# HS_MASTER_V3.net
KiCad netlist of a schematic drawn in EAGLE
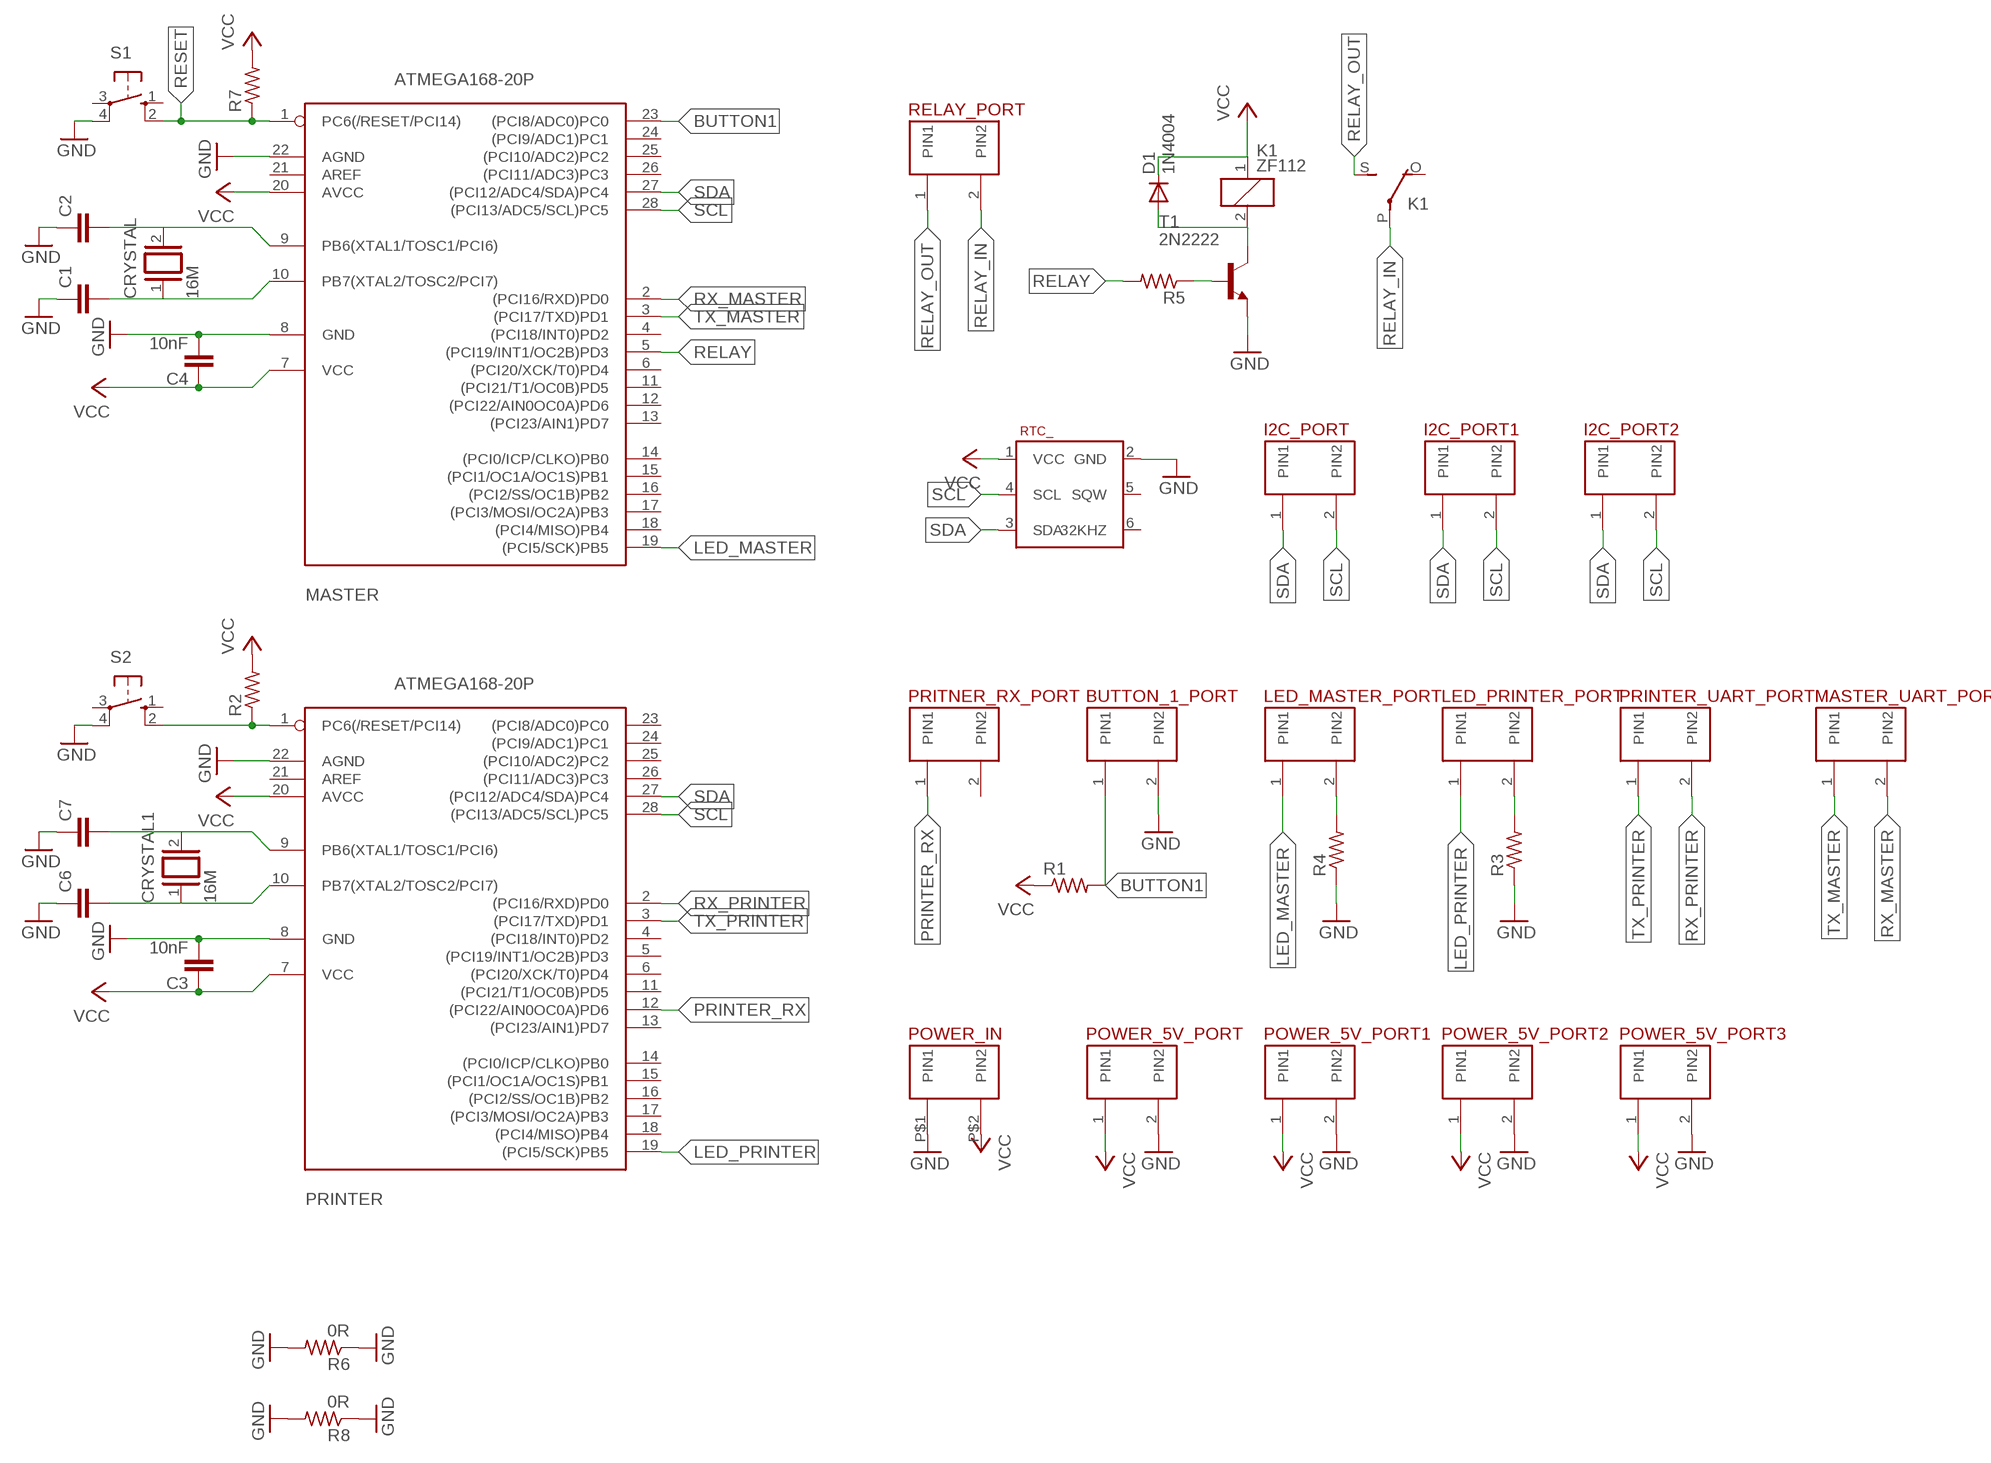
[diagram p0: schematic, sheet 1]

(export (version "E")
  (design (tool "Eeschema 10.0.6"))
  (components
    (comp (ref "BUTTON_1_PORT")
      (value "7325")
      (footprint "eagle-import:2.54MM")
      (libsource (lib "eagle-import") (part "7325"))
    )
    (comp (ref "C1")
      (value "C-EU025-024X044")
      (footprint "eagle-import:C025-024X044")
      (libsource (lib "eagle-import") (part "C-EU025-024X044"))
    )
    (comp (ref "C2")
      (value "C-EU025-024X044")
      (footprint "eagle-import:C025-024X044")
      (libsource (lib "eagle-import") (part "C-EU025-024X044"))
    )
    (comp (ref "C3")
      (value "10nF")
      (footprint "eagle-import:C5B2.5")
      (libsource (lib "eagle-import") (part "C5/2.5"))
    )
    (comp (ref "C4")
      (value "10nF")
      (footprint "eagle-import:C5B2.5")
      (libsource (lib "eagle-import") (part "C5/2.5"))
    )
    (comp (ref "C6")
      (value "C-EU025-024X044")
      (footprint "eagle-import:C025-024X044")
      (libsource (lib "eagle-import") (part "C-EU025-024X044"))
    )
    (comp (ref "C7")
      (value "C-EU025-024X044")
      (footprint "eagle-import:C025-024X044")
      (libsource (lib "eagle-import") (part "C-EU025-024X044"))
    )
    (comp (ref "CRYSTAL")
      (value "16M")
      (footprint "eagle-import:QS")
      (libsource (lib "eagle-import") (part "XTAL/S"))
    )
    (comp (ref "CRYSTAL1")
      (value "16M")
      (footprint "eagle-import:QS")
      (libsource (lib "eagle-import") (part "XTAL/S"))
    )
    (comp (ref "D1")
      (value "1N4004")
      (footprint "eagle-import:DO41-10")
      (libsource (lib "eagle-import") (part "1N4004"))
    )
    (comp (ref "I2C_PORT")
      (value "7325")
      (footprint "eagle-import:2.54MM")
      (libsource (lib "eagle-import") (part "7325"))
    )
    (comp (ref "I2C_PORT1")
      (value "7325")
      (footprint "eagle-import:2.54MM")
      (libsource (lib "eagle-import") (part "7325"))
    )
    (comp (ref "I2C_PORT2")
      (value "7325")
      (footprint "eagle-import:2.54MM")
      (libsource (lib "eagle-import") (part "7325"))
    )
    (comp (ref "K1")
      (value "ZF112")
      (footprint "eagle-import:ZF112")
      (libsource (lib "eagle-import") (part "ZF112"))
    )
    (comp (ref "LED_MASTER_PORT")
      (value "7325")
      (footprint "eagle-import:2.54MM")
      (libsource (lib "eagle-import") (part "7325"))
    )
    (comp (ref "LED_PRINTER_PORT")
      (value "7325")
      (footprint "eagle-import:2.54MM")
      (libsource (lib "eagle-import") (part "7325"))
    )
    (comp (ref "MASTER")
      (value "ATMEGA168-20P")
      (footprint "eagle-import:DIL28-3")
      (libsource (lib "eagle-import") (part "ATMEGA168P-20"))
    )
    (comp (ref "MASTER_UART_PORT")
      (value "7325")
      (footprint "eagle-import:2.54MM")
      (libsource (lib "eagle-import") (part "7325"))
    )
    (comp (ref "POWER_5V_PORT")
      (value "7325")
      (footprint "eagle-import:2.54MM")
      (libsource (lib "eagle-import") (part "7325"))
    )
    (comp (ref "POWER_5V_PORT1")
      (value "7325")
      (footprint "eagle-import:2.54MM")
      (libsource (lib "eagle-import") (part "7325"))
    )
    (comp (ref "POWER_5V_PORT2")
      (value "7325")
      (footprint "eagle-import:2.54MM")
      (libsource (lib "eagle-import") (part "7325"))
    )
    (comp (ref "POWER_5V_PORT3")
      (value "7325")
      (footprint "eagle-import:2.54MM")
      (libsource (lib "eagle-import") (part "7325"))
    )
    (comp (ref "POWER_IN")
      (value "4396")
      (footprint "eagle-import:4MM")
      (libsource (lib "eagle-import") (part "4396"))
    )
    (comp (ref "PRINTER")
      (value "ATMEGA168-20P")
      (footprint "eagle-import:DIL28-3")
      (libsource (lib "eagle-import") (part "ATMEGA168P-20"))
    )
    (comp (ref "PRINTER_UART_PORT")
      (value "7325")
      (footprint "eagle-import:2.54MM")
      (libsource (lib "eagle-import") (part "7325"))
    )
    (comp (ref "PRITNER_RX_PORT")
      (value "7325")
      (footprint "eagle-import:2.54MM")
      (libsource (lib "eagle-import") (part "7325"))
    )
    (comp (ref "R1")
      (value "R-US_0207/10")
      (footprint "eagle-import:0207_10")
      (libsource (lib "eagle-import") (part "R-US_0207/10"))
    )
    (comp (ref "R2")
      (value "R-US_0207/10")
      (footprint "eagle-import:0207_10")
      (libsource (lib "eagle-import") (part "R-US_0207/10"))
    )
    (comp (ref "R3")
      (value "R-US_0207/10")
      (footprint "eagle-import:0207_10")
      (libsource (lib "eagle-import") (part "R-US_0207/10"))
    )
    (comp (ref "R4")
      (value "R-US_0207/10")
      (footprint "eagle-import:0207_10")
      (libsource (lib "eagle-import") (part "R-US_0207/10"))
    )
    (comp (ref "R5")
      (value "R-US_0207/10")
      (footprint "eagle-import:0207_10")
      (libsource (lib "eagle-import") (part "R-US_0207/10"))
    )
    (comp (ref "R6")
      (value "0R")
      (footprint "eagle-import:0207_10")
      (libsource (lib "eagle-import") (part "R-US_0207/10"))
    )
    (comp (ref "R7")
      (value "R-US_0207/10")
      (footprint "eagle-import:0207_10")
      (libsource (lib "eagle-import") (part "R-US_0207/10"))
    )
    (comp (ref "R8")
      (value "0R")
      (footprint "eagle-import:0207_10")
      (libsource (lib "eagle-import") (part "R-US_0207/10"))
    )
    (comp (ref "RELAY_PORT")
      (value "7325")
      (footprint "eagle-import:2.54MM")
      (libsource (lib "eagle-import") (part "7325"))
    )
    (comp (ref "RTC_")
      (value "RTC_DS3231_6_PIN")
      (footprint "eagle-import:RTC_DS3231_6_PIN")
      (libsource (lib "eagle-import") (part "RTC_DS3231_6_PIN"))
    )
    (comp (ref "S1")
      (value "10-XX")
      (footprint "eagle-import:B3F-10XX")
      (fields (field (name "MPN") "B3F-1000"))
      (libsource (lib "eagle-import") (part "10-XX"))
    )
    (comp (ref "S2")
      (value "10-XX")
      (footprint "eagle-import:B3F-10XX")
      (fields (field (name "MPN") "B3F-1000"))
      (libsource (lib "eagle-import") (part "10-XX"))
    )
    (comp (ref "T1")
      (value "2N2222")
      (footprint "eagle-import:TO92-EBC-OVAL")
      (libsource (lib "eagle-import") (part "2N2222"))
    )
  )
  (nets
    (net (code "1") (name "BUTTON1") (class "Default")
      (node (ref "BUTTON_1_PORT") (pin "1") (pinfunction "PIN1_1") (pintype "bidirectional"))
      (node (ref "MASTER") (pin "23") (pinfunction "(PCI8/ADC0)PC0_23") (pintype "bidirectional"))
      (node (ref "R1") (pin "2") (pinfunction "2_2") (pintype "passive"))
    )
    (net (code "2") (name "GND") (class "Default")
      (node (ref "BUTTON_1_PORT") (pin "2") (pinfunction "PIN2_2") (pintype "bidirectional"))
      (node (ref "C1") (pin "1") (pinfunction "1_1") (pintype "passive"))
      (node (ref "C2") (pin "1") (pinfunction "1_1") (pintype "passive"))
      (node (ref "C3") (pin "2") (pinfunction "2_2") (pintype "passive"))
      (node (ref "C4") (pin "2") (pinfunction "2_2") (pintype "passive"))
      (node (ref "C6") (pin "1") (pinfunction "1_1") (pintype "passive"))
      (node (ref "C7") (pin "1") (pinfunction "1_1") (pintype "passive"))
      (node (ref "MASTER") (pin "22") (pinfunction "AGND_22") (pintype "bidirectional"))
      (node (ref "MASTER") (pin "8") (pinfunction "GND_8") (pintype "bidirectional"))
      (node (ref "POWER_5V_PORT") (pin "2") (pinfunction "PIN2_2") (pintype "bidirectional"))
      (node (ref "POWER_5V_PORT1") (pin "2") (pinfunction "PIN2_2") (pintype "bidirectional"))
      (node (ref "POWER_5V_PORT2") (pin "2") (pinfunction "PIN2_2") (pintype "bidirectional"))
      (node (ref "POWER_5V_PORT3") (pin "2") (pinfunction "PIN2_2") (pintype "bidirectional"))
      (node (ref "POWER_IN") (pin "P$1") (pinfunction "PIN1_P$1") (pintype "bidirectional"))
      (node (ref "PRINTER") (pin "22") (pinfunction "AGND_22") (pintype "bidirectional"))
      (node (ref "PRINTER") (pin "8") (pinfunction "GND_8") (pintype "bidirectional"))
      (node (ref "R3") (pin "1") (pinfunction "1_1") (pintype "passive"))
      (node (ref "R4") (pin "1") (pinfunction "1_1") (pintype "passive"))
      (node (ref "R6") (pin "1") (pinfunction "1_1") (pintype "passive"))
      (node (ref "R6") (pin "2") (pinfunction "2_2") (pintype "passive"))
      (node (ref "R8") (pin "1") (pinfunction "1_1") (pintype "passive"))
      (node (ref "R8") (pin "2") (pinfunction "2_2") (pintype "passive"))
      (node (ref "RTC_") (pin "2") (pinfunction "GND_2") (pintype "bidirectional"))
      (node (ref "S1") (pin "4") (pinfunction "P1_4") (pintype "passive"))
      (node (ref "S2") (pin "4") (pinfunction "P1_4") (pintype "passive"))
      (node (ref "T1") (pin "E") (pinfunction "E_E") (pintype "passive"))
    )
    (net (code "3") (name "LED_MASTER") (class "Default")
      (node (ref "LED_MASTER_PORT") (pin "1") (pinfunction "PIN1_1") (pintype "bidirectional"))
      (node (ref "MASTER") (pin "19") (pinfunction "(PCI5/SCK)PB5_19") (pintype "bidirectional"))
    )
    (net (code "4") (name "LED_PRINTER") (class "Default")
      (node (ref "LED_PRINTER_PORT") (pin "1") (pinfunction "PIN1_1") (pintype "bidirectional"))
      (node (ref "PRINTER") (pin "19") (pinfunction "(PCI5/SCK)PB5_19") (pintype "bidirectional"))
    )
    (net (code "5") (name "Net-(D1-PadA)") (class "Default")
      (node (ref "D1") (pin "A") (pinfunction "A_A") (pintype "passive"))
      (node (ref "K1") (pin "2") (pinfunction "2_2") (pintype "passive"))
      (node (ref "T1") (pin "C") (pinfunction "C_C") (pintype "passive"))
    )
    (net (code "6") (name "Net-(LED_MASTER_PORT-PIN2)") (class "Default")
      (node (ref "LED_MASTER_PORT") (pin "2") (pinfunction "PIN2_2") (pintype "bidirectional"))
      (node (ref "R4") (pin "2") (pinfunction "2_2") (pintype "passive"))
    )
    (net (code "7") (name "Net-(LED_PRINTER_PORT-PIN2)") (class "Default")
      (node (ref "LED_PRINTER_PORT") (pin "2") (pinfunction "PIN2_2") (pintype "bidirectional"))
      (node (ref "R3") (pin "2") (pinfunction "2_2") (pintype "passive"))
    )
    (net (code "8") (name "Net-(MASTER-PB6(XTAL1{slash}TOSC1{slash}PCI6))") (class "Default")
      (node (ref "C2") (pin "2") (pinfunction "2_2") (pintype "passive"))
      (node (ref "CRYSTAL") (pin "2") (pinfunction "2_2") (pintype "passive"))
      (node (ref "MASTER") (pin "9") (pinfunction "PB6(XTAL1/TOSC1/PCI6)_9") (pintype "bidirectional"))
    )
    (net (code "9") (name "Net-(MASTER-PB7(XTAL2{slash}TOSC2{slash}PCI7))") (class "Default")
      (node (ref "C1") (pin "2") (pinfunction "2_2") (pintype "passive"))
      (node (ref "CRYSTAL") (pin "1") (pinfunction "1_1") (pintype "passive"))
      (node (ref "MASTER") (pin "10") (pinfunction "PB7(XTAL2/TOSC2/PCI7)_10") (pintype "bidirectional"))
    )
    (net (code "10") (name "Net-(PRINTER-PB6(XTAL1{slash}TOSC1{slash}PCI6))") (class "Default")
      (node (ref "C7") (pin "2") (pinfunction "2_2") (pintype "passive"))
      (node (ref "CRYSTAL1") (pin "2") (pinfunction "2_2") (pintype "passive"))
      (node (ref "PRINTER") (pin "9") (pinfunction "PB6(XTAL1/TOSC1/PCI6)_9") (pintype "bidirectional"))
    )
    (net (code "11") (name "Net-(PRINTER-PB7(XTAL2{slash}TOSC2{slash}PCI7))") (class "Default")
      (node (ref "C6") (pin "2") (pinfunction "2_2") (pintype "passive"))
      (node (ref "CRYSTAL1") (pin "1") (pinfunction "1_1") (pintype "passive"))
      (node (ref "PRINTER") (pin "10") (pinfunction "PB7(XTAL2/TOSC2/PCI7)_10") (pintype "bidirectional"))
    )
    (net (code "12") (name "Net-(PRINTER-PC6({slash}RESET{slash}PCI14))") (class "Default")
      (node (ref "PRINTER") (pin "1") (pinfunction "PC6(/RESET/PCI14)_1") (pintype "bidirectional"))
      (node (ref "R2") (pin "1") (pinfunction "1_1") (pintype "passive"))
      (node (ref "S2") (pin "2") (pinfunction "S1_2") (pintype "passive"))
    )
    (net (code "13") (name "Net-(R5-Pad1)") (class "Default")
      (node (ref "R5") (pin "1") (pinfunction "1_1") (pintype "passive"))
      (node (ref "T1") (pin "B") (pinfunction "B_B") (pintype "passive"))
    )
    (net (code "14") (name "PRINTER_RX") (class "Default")
      (node (ref "PRINTER") (pin "12") (pinfunction "(PCI22/AIN0OC0A)PD6_12") (pintype "bidirectional"))
      (node (ref "PRITNER_RX_PORT") (pin "1") (pinfunction "PIN1_1") (pintype "bidirectional"))
    )
    (net (code "15") (name "RELAY") (class "Default")
      (node (ref "MASTER") (pin "5") (pinfunction "(PCI19/INT1/OC2B)PD3_5") (pintype "bidirectional"))
      (node (ref "R5") (pin "2") (pinfunction "2_2") (pintype "passive"))
    )
    (net (code "16") (name "RELAY_IN") (class "Default")
      (node (ref "K1") (pin "P") (pinfunction "P_P") (pintype "passive"))
      (node (ref "RELAY_PORT") (pin "2") (pinfunction "PIN2_2") (pintype "bidirectional"))
    )
    (net (code "17") (name "RELAY_OUT") (class "Default")
      (node (ref "K1") (pin "S") (pinfunction "S_S") (pintype "passive"))
      (node (ref "RELAY_PORT") (pin "1") (pinfunction "PIN1_1") (pintype "bidirectional"))
    )
    (net (code "18") (name "RESET") (class "Default")
      (node (ref "MASTER") (pin "1") (pinfunction "PC6(/RESET/PCI14)_1") (pintype "bidirectional"))
      (node (ref "R7") (pin "1") (pinfunction "1_1") (pintype "passive"))
      (node (ref "S1") (pin "2") (pinfunction "S1_2") (pintype "passive"))
    )
    (net (code "19") (name "RX_MASTER") (class "Default")
      (node (ref "MASTER") (pin "2") (pinfunction "(PCI16/RXD)PD0_2") (pintype "bidirectional"))
      (node (ref "MASTER_UART_PORT") (pin "2") (pinfunction "PIN2_2") (pintype "bidirectional"))
    )
    (net (code "20") (name "RX_PRINTER") (class "Default")
      (node (ref "PRINTER") (pin "2") (pinfunction "(PCI16/RXD)PD0_2") (pintype "bidirectional"))
      (node (ref "PRINTER_UART_PORT") (pin "2") (pinfunction "PIN2_2") (pintype "bidirectional"))
    )
    (net (code "21") (name "SCL") (class "Default")
      (node (ref "I2C_PORT") (pin "2") (pinfunction "PIN2_2") (pintype "bidirectional"))
      (node (ref "I2C_PORT1") (pin "2") (pinfunction "PIN2_2") (pintype "bidirectional"))
      (node (ref "I2C_PORT2") (pin "2") (pinfunction "PIN2_2") (pintype "bidirectional"))
      (node (ref "MASTER") (pin "28") (pinfunction "(PCI13/ADC5/SCL)PC5_28") (pintype "bidirectional"))
      (node (ref "PRINTER") (pin "28") (pinfunction "(PCI13/ADC5/SCL)PC5_28") (pintype "bidirectional"))
      (node (ref "RTC_") (pin "4") (pinfunction "SCL_4") (pintype "bidirectional"))
    )
    (net (code "22") (name "SDA") (class "Default")
      (node (ref "I2C_PORT") (pin "1") (pinfunction "PIN1_1") (pintype "bidirectional"))
      (node (ref "I2C_PORT1") (pin "1") (pinfunction "PIN1_1") (pintype "bidirectional"))
      (node (ref "I2C_PORT2") (pin "1") (pinfunction "PIN1_1") (pintype "bidirectional"))
      (node (ref "MASTER") (pin "27") (pinfunction "(PCI12/ADC4/SDA)PC4_27") (pintype "bidirectional"))
      (node (ref "PRINTER") (pin "27") (pinfunction "(PCI12/ADC4/SDA)PC4_27") (pintype "bidirectional"))
      (node (ref "RTC_") (pin "3") (pinfunction "SDA_3") (pintype "bidirectional"))
    )
    (net (code "23") (name "TX_MASTER") (class "Default")
      (node (ref "MASTER") (pin "3") (pinfunction "(PCI17/TXD)PD1_3") (pintype "bidirectional"))
      (node (ref "MASTER_UART_PORT") (pin "1") (pinfunction "PIN1_1") (pintype "bidirectional"))
    )
    (net (code "24") (name "TX_PRINTER") (class "Default")
      (node (ref "PRINTER") (pin "3") (pinfunction "(PCI17/TXD)PD1_3") (pintype "bidirectional"))
      (node (ref "PRINTER_UART_PORT") (pin "1") (pinfunction "PIN1_1") (pintype "bidirectional"))
    )
    (net (code "25") (name "VCC") (class "Default")
      (node (ref "C3") (pin "1") (pinfunction "1_1") (pintype "passive"))
      (node (ref "C4") (pin "1") (pinfunction "1_1") (pintype "passive"))
      (node (ref "D1") (pin "C") (pinfunction "C_C") (pintype "passive"))
      (node (ref "K1") (pin "1") (pinfunction "1_1") (pintype "passive"))
      (node (ref "MASTER") (pin "20") (pinfunction "AVCC_20") (pintype "bidirectional"))
      (node (ref "MASTER") (pin "7") (pinfunction "VCC_7") (pintype "bidirectional"))
      (node (ref "POWER_5V_PORT") (pin "1") (pinfunction "PIN1_1") (pintype "bidirectional"))
      (node (ref "POWER_5V_PORT1") (pin "1") (pinfunction "PIN1_1") (pintype "bidirectional"))
      (node (ref "POWER_5V_PORT2") (pin "1") (pinfunction "PIN1_1") (pintype "bidirectional"))
      (node (ref "POWER_5V_PORT3") (pin "1") (pinfunction "PIN1_1") (pintype "bidirectional"))
      (node (ref "POWER_IN") (pin "P$2") (pinfunction "PIN2_P$2") (pintype "bidirectional"))
      (node (ref "PRINTER") (pin "20") (pinfunction "AVCC_20") (pintype "bidirectional"))
      (node (ref "PRINTER") (pin "7") (pinfunction "VCC_7") (pintype "bidirectional"))
      (node (ref "R1") (pin "1") (pinfunction "1_1") (pintype "passive"))
      (node (ref "R2") (pin "2") (pinfunction "2_2") (pintype "passive"))
      (node (ref "R7") (pin "2") (pinfunction "2_2") (pintype "passive"))
      (node (ref "RTC_") (pin "1") (pinfunction "VCC_1") (pintype "bidirectional"))
    )
    (net (code "26") (name "unconnected-(K1-PadO)") (class "Default")
      (node (ref "K1") (pin "O") (pinfunction "O_O") (pintype "passive"))
    )
    (net (code "27") (name "unconnected-(MASTER-(PCI0{slash}ICP{slash}CLKO)PB0-Pad14)") (class "Default")
      (node (ref "MASTER") (pin "14") (pinfunction "(PCI0/ICP/CLKO)PB0_14") (pintype "bidirectional"))
    )
    (net (code "28") (name "unconnected-(MASTER-(PCI1{slash}OC1A{slash}OC1S)PB1-Pad15)") (class "Default")
      (node (ref "MASTER") (pin "15") (pinfunction "(PCI1/OC1A/OC1S)PB1_15") (pintype "bidirectional"))
    )
    (net (code "29") (name "unconnected-(MASTER-(PCI2{slash}SS{slash}OC1B)PB2-Pad16)") (class "Default")
      (node (ref "MASTER") (pin "16") (pinfunction "(PCI2/SS/OC1B)PB2_16") (pintype "bidirectional"))
    )
    (net (code "30") (name "unconnected-(MASTER-(PCI3{slash}MOSI{slash}OC2A)PB3-Pad17)") (class "Default")
      (node (ref "MASTER") (pin "17") (pinfunction "(PCI3/MOSI/OC2A)PB3_17") (pintype "bidirectional"))
    )
    (net (code "31") (name "unconnected-(MASTER-(PCI4{slash}MISO)PB4-Pad18)") (class "Default")
      (node (ref "MASTER") (pin "18") (pinfunction "(PCI4/MISO)PB4_18") (pintype "bidirectional"))
    )
    (net (code "32") (name "unconnected-(MASTER-(PCI9{slash}ADC1)PC1-Pad24)") (class "Default")
      (node (ref "MASTER") (pin "24") (pinfunction "(PCI9/ADC1)PC1_24") (pintype "bidirectional"))
    )
    (net (code "33") (name "unconnected-(MASTER-(PCI10{slash}ADC2)PC2-Pad25)") (class "Default")
      (node (ref "MASTER") (pin "25") (pinfunction "(PCI10/ADC2)PC2_25") (pintype "bidirectional"))
    )
    (net (code "34") (name "unconnected-(MASTER-(PCI11{slash}ADC3)PC3-Pad26)") (class "Default")
      (node (ref "MASTER") (pin "26") (pinfunction "(PCI11/ADC3)PC3_26") (pintype "bidirectional"))
    )
    (net (code "35") (name "unconnected-(MASTER-(PCI18{slash}INT0)PD2-Pad4)") (class "Default")
      (node (ref "MASTER") (pin "4") (pinfunction "(PCI18/INT0)PD2_4") (pintype "bidirectional"))
    )
    (net (code "36") (name "unconnected-(MASTER-(PCI20{slash}XCK{slash}T0)PD4-Pad6)") (class "Default")
      (node (ref "MASTER") (pin "6") (pinfunction "(PCI20/XCK/T0)PD4_6") (pintype "bidirectional"))
    )
    (net (code "37") (name "unconnected-(MASTER-(PCI21{slash}T1{slash}OC0B)PD5-Pad11)") (class "Default")
      (node (ref "MASTER") (pin "11") (pinfunction "(PCI21/T1/OC0B)PD5_11") (pintype "bidirectional"))
    )
    (net (code "38") (name "unconnected-(MASTER-(PCI22{slash}AIN0OC0A)PD6-Pad12)") (class "Default")
      (node (ref "MASTER") (pin "12") (pinfunction "(PCI22/AIN0OC0A)PD6_12") (pintype "bidirectional"))
    )
    (net (code "39") (name "unconnected-(MASTER-(PCI23{slash}AIN1)PD7-Pad13)") (class "Default")
      (node (ref "MASTER") (pin "13") (pinfunction "(PCI23/AIN1)PD7_13") (pintype "bidirectional"))
    )
    (net (code "40") (name "unconnected-(MASTER-AREF-Pad21)") (class "Default")
      (node (ref "MASTER") (pin "21") (pinfunction "AREF_21") (pintype "bidirectional"))
    )
    (net (code "41") (name "unconnected-(PRINTER-(PCI0{slash}ICP{slash}CLKO)PB0-Pad14)") (class "Default")
      (node (ref "PRINTER") (pin "14") (pinfunction "(PCI0/ICP/CLKO)PB0_14") (pintype "bidirectional"))
    )
    (net (code "42") (name "unconnected-(PRINTER-(PCI1{slash}OC1A{slash}OC1S)PB1-Pad15)") (class "Default")
      (node (ref "PRINTER") (pin "15") (pinfunction "(PCI1/OC1A/OC1S)PB1_15") (pintype "bidirectional"))
    )
    (net (code "43") (name "unconnected-(PRINTER-(PCI2{slash}SS{slash}OC1B)PB2-Pad16)") (class "Default")
      (node (ref "PRINTER") (pin "16") (pinfunction "(PCI2/SS/OC1B)PB2_16") (pintype "bidirectional"))
    )
    (net (code "44") (name "unconnected-(PRINTER-(PCI3{slash}MOSI{slash}OC2A)PB3-Pad17)") (class "Default")
      (node (ref "PRINTER") (pin "17") (pinfunction "(PCI3/MOSI/OC2A)PB3_17") (pintype "bidirectional"))
    )
    (net (code "45") (name "unconnected-(PRINTER-(PCI4{slash}MISO)PB4-Pad18)") (class "Default")
      (node (ref "PRINTER") (pin "18") (pinfunction "(PCI4/MISO)PB4_18") (pintype "bidirectional"))
    )
    (net (code "46") (name "unconnected-(PRINTER-(PCI8{slash}ADC0)PC0-Pad23)") (class "Default")
      (node (ref "PRINTER") (pin "23") (pinfunction "(PCI8/ADC0)PC0_23") (pintype "bidirectional"))
    )
    (net (code "47") (name "unconnected-(PRINTER-(PCI9{slash}ADC1)PC1-Pad24)") (class "Default")
      (node (ref "PRINTER") (pin "24") (pinfunction "(PCI9/ADC1)PC1_24") (pintype "bidirectional"))
    )
    (net (code "48") (name "unconnected-(PRINTER-(PCI10{slash}ADC2)PC2-Pad25)") (class "Default")
      (node (ref "PRINTER") (pin "25") (pinfunction "(PCI10/ADC2)PC2_25") (pintype "bidirectional"))
    )
    (net (code "49") (name "unconnected-(PRINTER-(PCI11{slash}ADC3)PC3-Pad26)") (class "Default")
      (node (ref "PRINTER") (pin "26") (pinfunction "(PCI11/ADC3)PC3_26") (pintype "bidirectional"))
    )
    (net (code "50") (name "unconnected-(PRINTER-(PCI18{slash}INT0)PD2-Pad4)") (class "Default")
      (node (ref "PRINTER") (pin "4") (pinfunction "(PCI18/INT0)PD2_4") (pintype "bidirectional"))
    )
    (net (code "51") (name "unconnected-(PRINTER-(PCI19{slash}INT1{slash}OC2B)PD3-Pad5)") (class "Default")
      (node (ref "PRINTER") (pin "5") (pinfunction "(PCI19/INT1/OC2B)PD3_5") (pintype "bidirectional"))
    )
    (net (code "52") (name "unconnected-(PRINTER-(PCI20{slash}XCK{slash}T0)PD4-Pad6)") (class "Default")
      (node (ref "PRINTER") (pin "6") (pinfunction "(PCI20/XCK/T0)PD4_6") (pintype "bidirectional"))
    )
    (net (code "53") (name "unconnected-(PRINTER-(PCI21{slash}T1{slash}OC0B)PD5-Pad11)") (class "Default")
      (node (ref "PRINTER") (pin "11") (pinfunction "(PCI21/T1/OC0B)PD5_11") (pintype "bidirectional"))
    )
    (net (code "54") (name "unconnected-(PRINTER-(PCI23{slash}AIN1)PD7-Pad13)") (class "Default")
      (node (ref "PRINTER") (pin "13") (pinfunction "(PCI23/AIN1)PD7_13") (pintype "bidirectional"))
    )
    (net (code "55") (name "unconnected-(PRINTER-AREF-Pad21)") (class "Default")
      (node (ref "PRINTER") (pin "21") (pinfunction "AREF_21") (pintype "bidirectional"))
    )
    (net (code "56") (name "unconnected-(PRITNER_RX_PORT-PIN2-Pad2)") (class "Default")
      (node (ref "PRITNER_RX_PORT") (pin "2") (pinfunction "PIN2_2") (pintype "bidirectional"))
    )
    (net (code "57") (name "unconnected-(RTC_-32KHZ-Pad6)") (class "Default")
      (node (ref "RTC_") (pin "6") (pinfunction "32KHZ_6") (pintype "bidirectional"))
    )
    (net (code "58") (name "unconnected-(RTC_-SQW-Pad5)") (class "Default")
      (node (ref "RTC_") (pin "5") (pinfunction "SQW_5") (pintype "bidirectional"))
    )
    (net (code "59") (name "unconnected-(S1-P-Pad3)") (class "Default")
      (node (ref "S1") (pin "3") (pinfunction "P_3") (pintype "passive"))
    )
    (net (code "60") (name "unconnected-(S1-S-Pad1)") (class "Default")
      (node (ref "S1") (pin "1") (pinfunction "S_1") (pintype "passive"))
    )
    (net (code "61") (name "unconnected-(S2-P-Pad3)") (class "Default")
      (node (ref "S2") (pin "3") (pinfunction "P_3") (pintype "passive"))
    )
    (net (code "62") (name "unconnected-(S2-S-Pad1)") (class "Default")
      (node (ref "S2") (pin "1") (pinfunction "S_1") (pintype "passive"))
    )
  )
)
